# bluepill-knx-transceiver.net
KiCad netlist of a schematic drawn in EAGLE
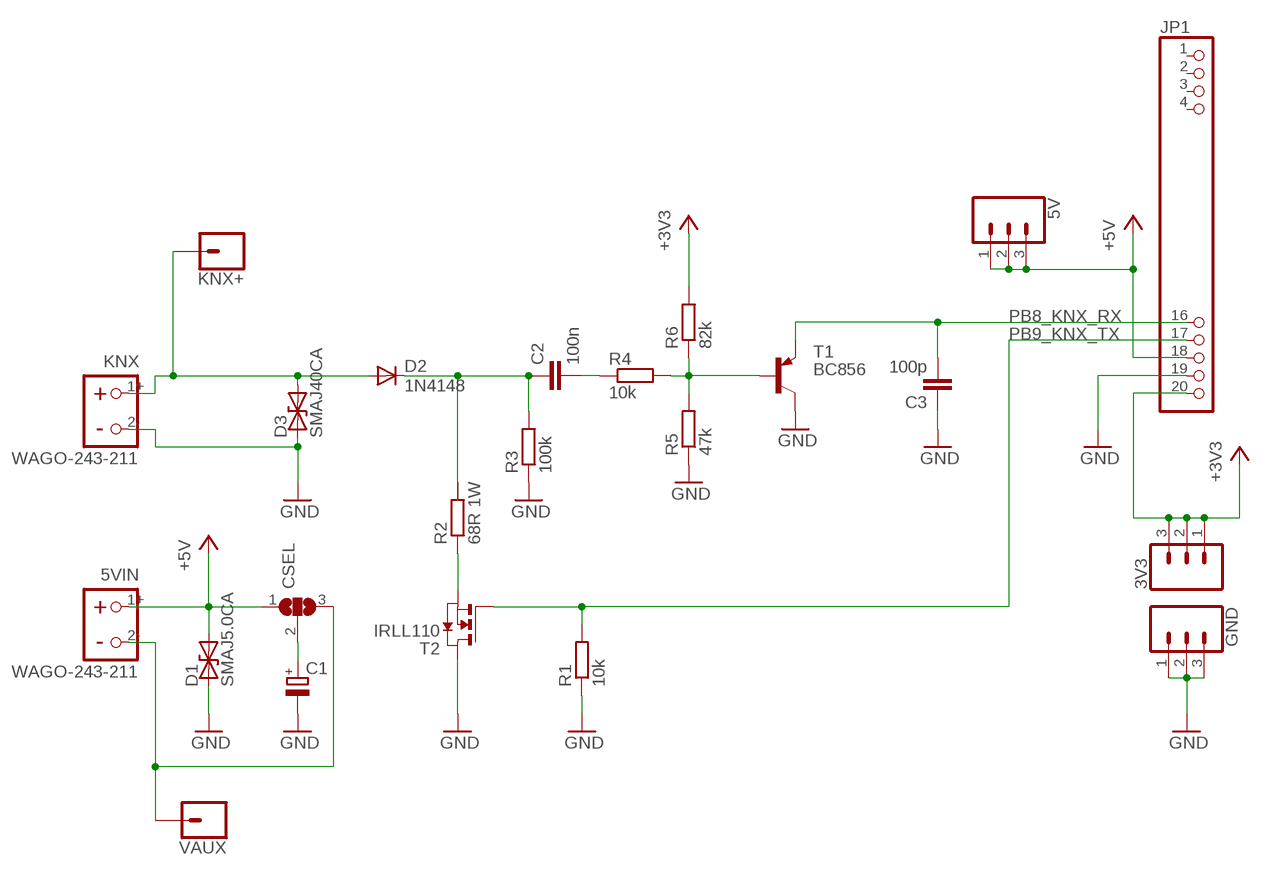
[diagram p0: schematic, sheet 1]

(export (version "E")
  (design (tool "Eeschema 10.0.6"))
  (components
    (comp (ref "3V3")
      (value "CONN_03")
      (footprint "eagle-import:1X03")
      (libsource (lib "eagle-import") (part "CONN_03"))
    )
    (comp (ref "5V")
      (value "CONN_03")
      (footprint "eagle-import:1X03")
      (libsource (lib "eagle-import") (part "CONN_03"))
    )
    (comp (ref "5VIN")
      (value "WAGO-243-211")
      (footprint "eagle-import:WAGO-243-211")
      (libsource (lib "eagle-import") (part "WAGO-243-211"))
    )
    (comp (ref "C1")
      (value "CPOL-EUE3.5-8")
      (footprint "eagle-import:E3,5-8")
      (libsource (lib "eagle-import") (part "CPOL-EUE3.5-8"))
    )
    (comp (ref "C2")
      (value "100n")
      (footprint "eagle-import:C1206")
      (libsource (lib "eagle-import") (part "C-EUC1206"))
    )
    (comp (ref "C3")
      (value "100p")
      (footprint "eagle-import:C1206")
      (libsource (lib "eagle-import") (part "C-EUC1206"))
    )
    (comp (ref "CSEL")
      (value "SJ2W")
      (footprint "eagle-import:SJ_2")
      (libsource (lib "eagle-import") (part "SJ2W"))
    )
    (comp (ref "D1")
      (value "SMAJ5.0CA")
      (footprint "eagle-import:DO-214AC")
      (libsource (lib "eagle-import") (part "SMAJ40AC"))
    )
    (comp (ref "D2")
      (value "1N4148")
      (footprint "eagle-import:MINIMELF")
      (libsource (lib "eagle-import") (part "DIODE-MINIMELF"))
    )
    (comp (ref "D3")
      (value "SMAJ40CA")
      (footprint "eagle-import:DO-214AC")
      (libsource (lib "eagle-import") (part "SMAJ40AC"))
    )
    (comp (ref "GND")
      (value "CONN_03")
      (footprint "eagle-import:1X03")
      (libsource (lib "eagle-import") (part "CONN_03"))
    )
    (comp (ref "JP1")
      (value "PINHD-1X20-BP")
      (footprint "eagle-import:1X20-BP")
      (libsource (lib "eagle-import") (part "PINHD-1X20-BP"))
    )
    (comp (ref "KNX")
      (value "WAGO-243-211")
      (footprint "eagle-import:WAGO-243-211")
      (libsource (lib "eagle-import") (part "WAGO-243-211"))
    )
    (comp (ref "KNX+")
      (value "CONN_01")
      (footprint "eagle-import:1X01")
      (libsource (lib "eagle-import") (part "CONN_01"))
    )
    (comp (ref "R1")
      (value "10k")
      (footprint "eagle-import:R1206")
      (libsource (lib "eagle-import") (part "R-EU_R1206"))
    )
    (comp (ref "R2")
      (value "68R 1W")
      (footprint "eagle-import:R2512")
      (libsource (lib "eagle-import") (part "rcl_334_R-EU_R2512"))
    )
    (comp (ref "R3")
      (value "100k")
      (footprint "eagle-import:R1206")
      (libsource (lib "eagle-import") (part "R-EU_R1206"))
    )
    (comp (ref "R4")
      (value "10k")
      (footprint "eagle-import:R1206")
      (libsource (lib "eagle-import") (part "R-EU_R1206"))
    )
    (comp (ref "R5")
      (value "47k")
      (footprint "eagle-import:R1206")
      (libsource (lib "eagle-import") (part "R-EU_R1206"))
    )
    (comp (ref "R6")
      (value "82k")
      (footprint "eagle-import:R1206")
      (libsource (lib "eagle-import") (part "R-EU_R1206"))
    )
    (comp (ref "T1")
      (value "BC856")
      (footprint "eagle-import:SOT23-BEC")
      (libsource (lib "eagle-import") (part "BC856SMDB"))
    )
    (comp (ref "T2")
      (value "IRLL110")
      (footprint "eagle-import:SOT223")
      (libsource (lib "eagle-import") (part "NMOSSOT223"))
    )
    (comp (ref "VAUX")
      (value "CONN_01")
      (footprint "eagle-import:1X01")
      (libsource (lib "eagle-import") (part "CONN_01"))
    )
  )
  (nets
    (net (code "1") (name "+3V3") (class "Default")
      (node (ref "3V3") (pin "1") (pinfunction "1_1") (pintype "passive"))
      (node (ref "3V3") (pin "2") (pinfunction "2_2") (pintype "passive"))
      (node (ref "3V3") (pin "3") (pinfunction "3_3") (pintype "passive"))
      (node (ref "JP1") (pin "20") (pinfunction "20_20") (pintype "passive"))
      (node (ref "R6") (pin "2") (pinfunction "2_2") (pintype "passive"))
    )
    (net (code "2") (name "+5V") (class "Default")
      (node (ref "5V") (pin "1") (pinfunction "1_1") (pintype "passive"))
      (node (ref "5V") (pin "2") (pinfunction "2_2") (pintype "passive"))
      (node (ref "5V") (pin "3") (pinfunction "3_3") (pintype "passive"))
      (node (ref "5VIN") (pin "1+") (pinfunction "1+_1+") (pintype "passive"))
      (node (ref "CSEL") (pin "1") (pinfunction "1_1") (pintype "passive"))
      (node (ref "D1") (pin "C") (pinfunction "C_C") (pintype "passive"))
      (node (ref "JP1") (pin "18") (pinfunction "18_18") (pintype "passive"))
    )
    (net (code "3") (name "/PB8_KNX_RX") (class "Default")
      (node (ref "C3") (pin "2") (pinfunction "2_2") (pintype "passive"))
      (node (ref "JP1") (pin "16") (pinfunction "16_16") (pintype "passive"))
      (node (ref "T1") (pin "E") (pinfunction "E_E") (pintype "passive"))
    )
    (net (code "4") (name "/PB9_KNX_TX") (class "Default")
      (node (ref "JP1") (pin "17") (pinfunction "17_17") (pintype "passive"))
      (node (ref "R1") (pin "2") (pinfunction "2_2") (pintype "passive"))
      (node (ref "T2") (pin "1") (pinfunction "G_1") (pintype "passive"))
    )
    (net (code "5") (name "GND") (class "Default")
      (node (ref "C1") (pin "-") (pinfunction "-_-") (pintype "passive"))
      (node (ref "C3") (pin "1") (pinfunction "1_1") (pintype "passive"))
      (node (ref "D1") (pin "A") (pinfunction "A_A") (pintype "passive"))
      (node (ref "D3") (pin "A") (pinfunction "A_A") (pintype "passive"))
      (node (ref "GND") (pin "1") (pinfunction "1_1") (pintype "passive"))
      (node (ref "GND") (pin "2") (pinfunction "2_2") (pintype "passive"))
      (node (ref "GND") (pin "3") (pinfunction "3_3") (pintype "passive"))
      (node (ref "JP1") (pin "19") (pinfunction "19_19") (pintype "passive"))
      (node (ref "KNX") (pin "2-") (pinfunction "2-_2-") (pintype "passive"))
      (node (ref "R1") (pin "1") (pinfunction "1_1") (pintype "passive"))
      (node (ref "R3") (pin "1") (pinfunction "1_1") (pintype "passive"))
      (node (ref "R5") (pin "1") (pinfunction "1_1") (pintype "passive"))
      (node (ref "T1") (pin "C") (pinfunction "C_C") (pintype "passive"))
      (node (ref "T2") (pin "2") (pinfunction "D_2") (pintype "passive"))
      (node (ref "T2") (pin "4") (pinfunction "D_4") (pintype "passive"))
    )
    (net (code "6") (name "Net-(5VIN-Pad2-)") (class "Default")
      (node (ref "5VIN") (pin "2-") (pinfunction "2-_2-") (pintype "passive"))
      (node (ref "CSEL") (pin "3") (pinfunction "3_3") (pintype "passive"))
      (node (ref "VAUX") (pin "1") (pinfunction "1_1") (pintype "passive"))
    )
    (net (code "7") (name "Net-(C1-Pad+)") (class "Default")
      (node (ref "C1") (pin "+") (pinfunction "+_+") (pintype "passive"))
      (node (ref "CSEL") (pin "2") (pinfunction "2_2") (pintype "passive"))
    )
    (net (code "8") (name "Net-(C2-Pad1)") (class "Default")
      (node (ref "C2") (pin "1") (pinfunction "1_1") (pintype "passive"))
      (node (ref "D2") (pin "C") (pinfunction "C_C") (pintype "passive"))
      (node (ref "R2") (pin "2") (pinfunction "2_2") (pintype "passive"))
      (node (ref "R3") (pin "2") (pinfunction "2_2") (pintype "passive"))
    )
    (net (code "9") (name "Net-(C2-Pad2)") (class "Default")
      (node (ref "C2") (pin "2") (pinfunction "2_2") (pintype "passive"))
      (node (ref "R4") (pin "1") (pinfunction "1_1") (pintype "passive"))
    )
    (net (code "10") (name "Net-(D2-PadA)") (class "Default")
      (node (ref "D2") (pin "A") (pinfunction "A_A") (pintype "passive"))
      (node (ref "D3") (pin "C") (pinfunction "C_C") (pintype "passive"))
      (node (ref "KNX") (pin "1+") (pinfunction "1+_1+") (pintype "passive"))
      (node (ref "KNX+") (pin "1") (pinfunction "1_1") (pintype "passive"))
    )
    (net (code "11") (name "Net-(R4-Pad2)") (class "Default")
      (node (ref "R4") (pin "2") (pinfunction "2_2") (pintype "passive"))
      (node (ref "R5") (pin "2") (pinfunction "2_2") (pintype "passive"))
      (node (ref "R6") (pin "1") (pinfunction "1_1") (pintype "passive"))
      (node (ref "T1") (pin "B") (pinfunction "B_B") (pintype "passive"))
    )
    (net (code "12") (name "Net-(T2-S)") (class "Default")
      (node (ref "R2") (pin "1") (pinfunction "1_1") (pintype "passive"))
      (node (ref "T2") (pin "3") (pinfunction "S_3") (pintype "passive"))
    )
    (net (code "13") (name "unconnected-(JP1-Pad1)") (class "Default")
      (node (ref "JP1") (pin "1") (pinfunction "1_1") (pintype "passive"))
    )
    (net (code "14") (name "unconnected-(JP1-Pad2)") (class "Default")
      (node (ref "JP1") (pin "2") (pinfunction "2_2") (pintype "passive"))
    )
    (net (code "15") (name "unconnected-(JP1-Pad3)") (class "Default")
      (node (ref "JP1") (pin "3") (pinfunction "3_3") (pintype "passive"))
    )
    (net (code "16") (name "unconnected-(JP1-Pad4)") (class "Default")
      (node (ref "JP1") (pin "4") (pinfunction "4_4") (pintype "passive"))
    )
  )
)
